# 7_HDMI2.net
KiCad netlist of a schematic drawn in Altium Designer
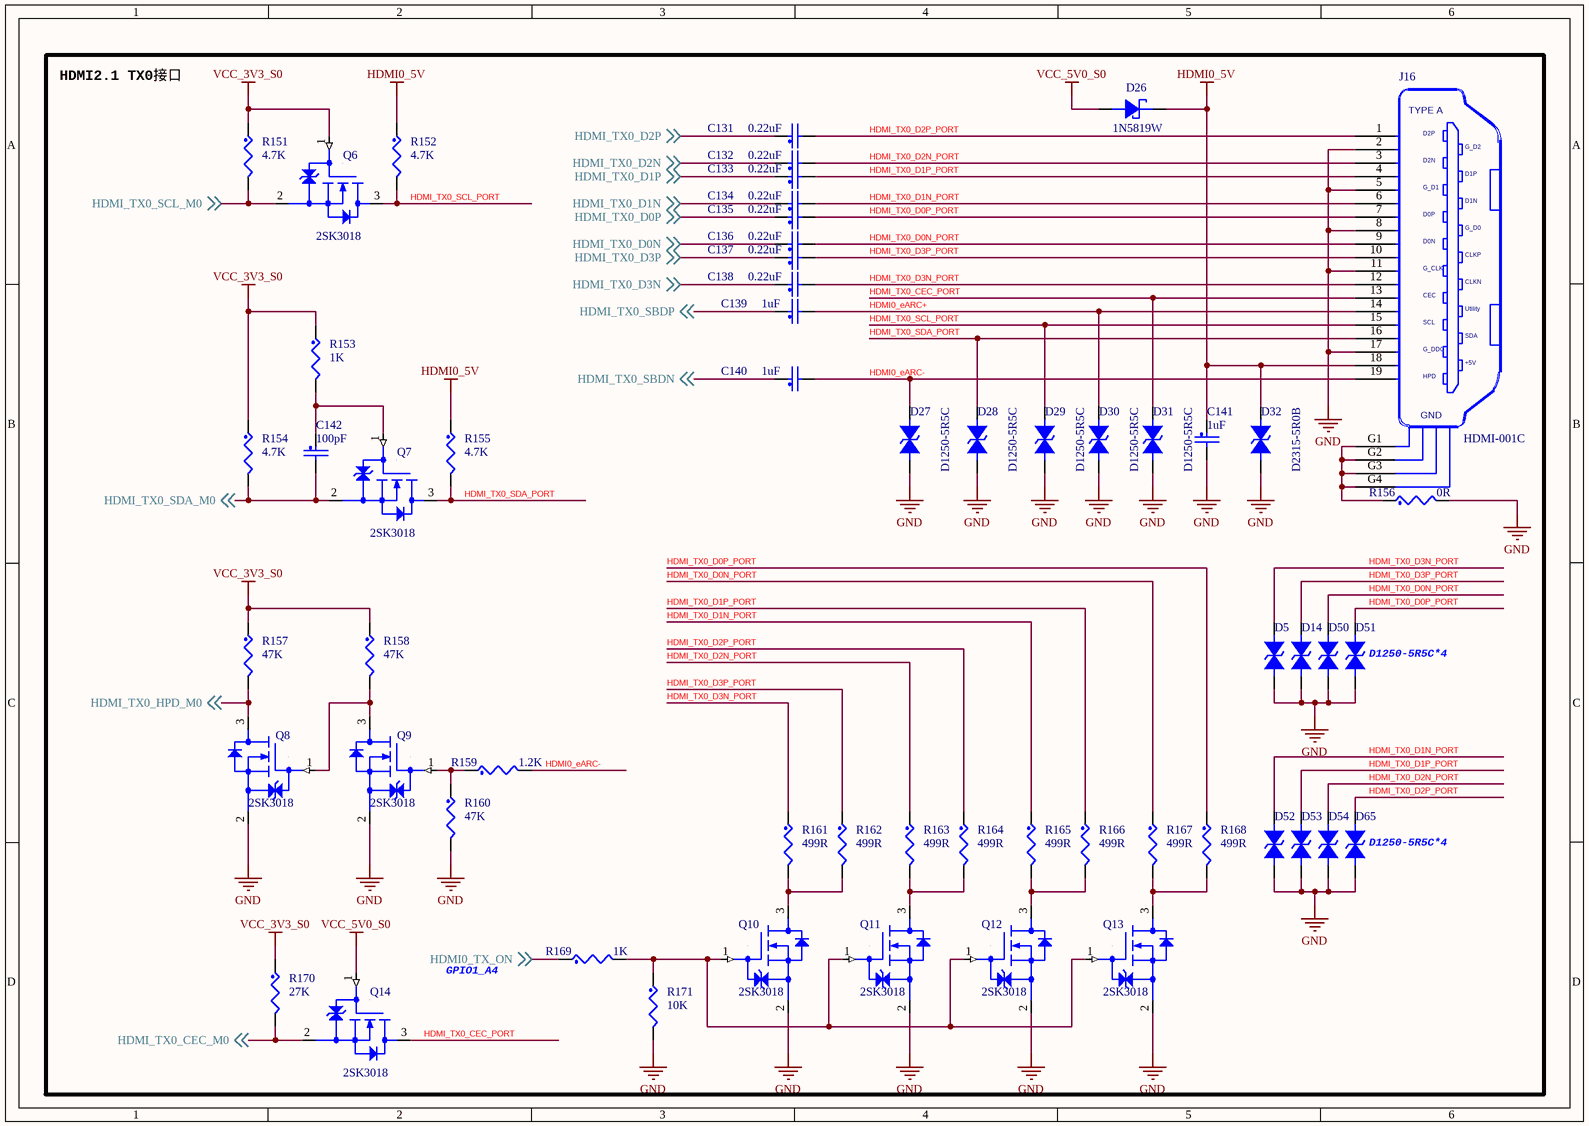
[diagram p0: 7.HDMI2.SchDoc]

(export (version "E")
  (design (tool "Eeschema 10.0.6"))
  (components
    (comp (ref "C131")
      (value "0.22uF")
      (footprint "0.PCB1:C0402")
      (libsource (lib "RK3588底板") (part "CAP_NP"))
    )
    (comp (ref "C132")
      (value "0.22uF")
      (footprint "0.PCB1:C0402")
      (libsource (lib "RK3588底板") (part "CAP_NP"))
    )
    (comp (ref "C133")
      (value "0.22uF")
      (footprint "0.PCB1:C0402")
      (libsource (lib "RK3588底板") (part "CAP_NP"))
    )
    (comp (ref "C134")
      (value "0.22uF")
      (footprint "0.PCB1:C0402")
      (libsource (lib "RK3588底板") (part "CAP_NP"))
    )
    (comp (ref "C135")
      (value "0.22uF")
      (footprint "0.PCB1:C0402")
      (libsource (lib "RK3588底板") (part "CAP_NP"))
    )
    (comp (ref "C136")
      (value "0.22uF")
      (footprint "0.PCB1:C0402")
      (libsource (lib "RK3588底板") (part "CAP_NP"))
    )
    (comp (ref "C137")
      (value "0.22uF")
      (footprint "0.PCB1:C0402")
      (libsource (lib "RK3588底板") (part "CAP_NP"))
    )
    (comp (ref "C138")
      (value "0.22uF")
      (footprint "0.PCB1:C0402")
      (libsource (lib "RK3588底板") (part "CAP_NP"))
    )
    (comp (ref "C139") (value "1uF") (footprint "0.PCB1:C0402") (libsource (lib "RK3588底板") (part "CAP_NP")))
    (comp (ref "C140") (value "1uF") (footprint "0.PCB1:C0402") (libsource (lib "RK3588底板") (part "CAP_NP")))
    (comp (ref "C141") (value "1uF") (footprint "0.PCB1:C0402") (libsource (lib "RK3588底板") (part "CAP_NP")))
    (comp (ref "C142")
      (value "100pF")
      (footprint "0.PCB1:C0402")
      (libsource (lib "RK3588底板") (part "CAP_NP"))
    )
    (comp (ref "D5")
      (value "D1250-5R5C")
      (footprint "0.PCB1:esd0402")
      (libsource (lib "RK3588底板") (part "DIODE BI-DIR TRIG"))
    )
    (comp (ref "D14")
      (value "D1250-5R5C")
      (footprint "0.PCB1:esd0402")
      (libsource (lib "RK3588底板") (part "DIODE BI-DIR TRIG"))
    )
    (comp (ref "D26")
      (value "1N5819W")
      (footprint "0.PCB1:SOD-123")
      (libsource (lib "RK3588底板") (part "DIODE_SCHTKY"))
    )
    (comp (ref "D27")
      (value "D1250-5R5C")
      (footprint "0.PCB1:esd0402")
      (libsource (lib "RK3588底板") (part "DIODE BI-DIR TRIG"))
    )
    (comp (ref "D28")
      (value "D1250-5R5C")
      (footprint "0.PCB1:esd0402")
      (libsource (lib "RK3588底板") (part "DIODE BI-DIR TRIG"))
    )
    (comp (ref "D29")
      (value "D1250-5R5C")
      (footprint "0.PCB1:esd0402")
      (libsource (lib "RK3588底板") (part "DIODE BI-DIR TRIG"))
    )
    (comp (ref "D30")
      (value "D1250-5R5C")
      (footprint "0.PCB1:esd0402")
      (libsource (lib "RK3588底板") (part "DIODE BI-DIR TRIG"))
    )
    (comp (ref "D31")
      (value "D1250-5R5C")
      (footprint "0.PCB1:esd0402")
      (libsource (lib "RK3588底板") (part "DIODE BI-DIR TRIG"))
    )
    (comp (ref "D32")
      (value "D2315-5R0B")
      (footprint "0.PCB1:esd0402")
      (libsource (lib "RK3588底板") (part "DIODE BI-DIR TRIG"))
    )
    (comp (ref "D50")
      (value "D1250-5R5C")
      (footprint "0.PCB1:esd0402")
      (libsource (lib "RK3588底板") (part "DIODE BI-DIR TRIG"))
    )
    (comp (ref "D51")
      (value "D1250-5R5C")
      (footprint "0.PCB1:esd0402")
      (libsource (lib "RK3588底板") (part "DIODE BI-DIR TRIG"))
    )
    (comp (ref "D52")
      (value "D1250-5R5C")
      (footprint "0.PCB1:esd0402")
      (libsource (lib "RK3588底板") (part "DIODE BI-DIR TRIG"))
    )
    (comp (ref "D53")
      (value "D1250-5R5C")
      (footprint "0.PCB1:esd0402")
      (libsource (lib "RK3588底板") (part "DIODE BI-DIR TRIG"))
    )
    (comp (ref "D54")
      (value "D1250-5R5C")
      (footprint "0.PCB1:esd0402")
      (libsource (lib "RK3588底板") (part "DIODE BI-DIR TRIG"))
    )
    (comp (ref "D65")
      (value "D1250-5R5C")
      (footprint "0.PCB1:esd0402")
      (libsource (lib "RK3588底板") (part "DIODE BI-DIR TRIG"))
    )
    (comp (ref "J16")
      (value "HDMI-001C")
      (footprint "0.PCB1:HDMI-SMD")
      (libsource (lib "RK3588底板") (part "HDMI-001C"))
    )
    (comp (ref "Q6")
      (value "2SK3018")
      (footprint "0.PCB1:SOT23")
      (libsource (lib "RK3588底板") (part "2SK3018"))
    )
    (comp (ref "Q7")
      (value "2SK3018")
      (footprint "0.PCB1:SOT23")
      (libsource (lib "RK3588底板") (part "2SK3018"))
    )
    (comp (ref "Q8")
      (value "2SK3018")
      (footprint "0.PCB1:SOT23")
      (libsource (lib "RK3588底板") (part "2SK3018"))
    )
    (comp (ref "Q9")
      (value "2SK3018")
      (footprint "0.PCB1:SOT23")
      (libsource (lib "RK3588底板") (part "2SK3018"))
    )
    (comp (ref "Q10")
      (value "2SK3018")
      (footprint "0.PCB1:SOT23")
      (libsource (lib "RK3588底板") (part "2SK3018"))
    )
    (comp (ref "Q11")
      (value "2SK3018")
      (footprint "0.PCB1:SOT23")
      (libsource (lib "RK3588底板") (part "2SK3018"))
    )
    (comp (ref "Q12")
      (value "2SK3018")
      (footprint "0.PCB1:SOT23")
      (libsource (lib "RK3588底板") (part "2SK3018"))
    )
    (comp (ref "Q13")
      (value "2SK3018")
      (footprint "0.PCB1:SOT23")
      (libsource (lib "RK3588底板") (part "2SK3018"))
    )
    (comp (ref "Q14")
      (value "2SK3018")
      (footprint "0.PCB1:SOT23")
      (libsource (lib "RK3588底板") (part "2SK3018"))
    )
    (comp (ref "R151") (value "4.7K") (footprint "0.PCB1:R0402") (libsource (lib "RK3588底板") (part "RES")))
    (comp (ref "R152") (value "4.7K") (footprint "0.PCB1:R0402") (libsource (lib "RK3588底板") (part "RES")))
    (comp (ref "R153") (value "1K") (footprint "0.PCB1:R0402") (libsource (lib "RK3588底板") (part "RES")))
    (comp (ref "R154") (value "4.7K") (footprint "0.PCB1:R0402") (libsource (lib "RK3588底板") (part "RES")))
    (comp (ref "R155") (value "4.7K") (footprint "0.PCB1:R0402") (libsource (lib "RK3588底板") (part "RES")))
    (comp (ref "R156") (value "0R") (footprint "0.PCB1:R0402") (libsource (lib "RK3588底板") (part "RES")))
    (comp (ref "R157") (value "47K") (footprint "0.PCB1:R0402") (libsource (lib "RK3588底板") (part "RES")))
    (comp (ref "R158") (value "47K") (footprint "0.PCB1:R0402") (libsource (lib "RK3588底板") (part "RES")))
    (comp (ref "R159") (value "1.2K") (footprint "0.PCB1:R0402") (libsource (lib "RK3588底板") (part "RES")))
    (comp (ref "R160") (value "47K") (footprint "0.PCB1:R0402") (libsource (lib "RK3588底板") (part "RES")))
    (comp (ref "R161") (value "499R") (footprint "0.PCB1:R0402") (libsource (lib "RK3588底板") (part "RES")))
    (comp (ref "R162") (value "499R") (footprint "0.PCB1:R0402") (libsource (lib "RK3588底板") (part "RES")))
    (comp (ref "R163") (value "499R") (footprint "0.PCB1:R0402") (libsource (lib "RK3588底板") (part "RES")))
    (comp (ref "R164") (value "499R") (footprint "0.PCB1:R0402") (libsource (lib "RK3588底板") (part "RES")))
    (comp (ref "R165") (value "499R") (footprint "0.PCB1:R0402") (libsource (lib "RK3588底板") (part "RES")))
    (comp (ref "R166") (value "499R") (footprint "0.PCB1:R0402") (libsource (lib "RK3588底板") (part "RES")))
    (comp (ref "R167") (value "499R") (footprint "0.PCB1:R0402") (libsource (lib "RK3588底板") (part "RES")))
    (comp (ref "R168") (value "499R") (footprint "0.PCB1:R0402") (libsource (lib "RK3588底板") (part "RES")))
    (comp (ref "R169") (value "1K") (footprint "0.PCB1:R0402") (libsource (lib "RK3588底板") (part "RES")))
    (comp (ref "R170") (value "27K") (footprint "0.PCB1:R0402") (libsource (lib "RK3588底板") (part "RES")))
    (comp (ref "R171") (value "10K") (footprint "0.PCB1:R0402") (libsource (lib "RK3588底板") (part "RES")))
  )
  (nets
    (net (code "1") (name "/HDMI0_eARC+") (class "Default")
      (node (ref "C139") (pin "2") (pinfunction "2_2") (pintype "passive"))
      (node (ref "D30") (pin "2") (pinfunction "2_2") (pintype "passive"))
      (node (ref "J16") (pin "14") (pinfunction "14_14") (pintype "passive"))
    )
    (net (code "2") (name "/HDMI0_eARC-") (class "Default")
      (node (ref "C140") (pin "2") (pinfunction "2_2") (pintype "passive"))
      (node (ref "D27") (pin "2") (pinfunction "2_2") (pintype "passive"))
      (node (ref "J16") (pin "19") (pinfunction "19_19") (pintype "passive"))
      (node (ref "R159") (pin "2") (pinfunction "2_2") (pintype "passive"))
    )
    (net (code "3") (name "/HDMI_TX0_CEC_PORT") (class "Default")
      (node (ref "D31") (pin "2") (pinfunction "2_2") (pintype "passive"))
      (node (ref "J16") (pin "13") (pinfunction "13_13") (pintype "passive"))
      (node (ref "Q14") (pin "3") (pinfunction "DRAIN_3") (pintype "passive"))
    )
    (net (code "4") (name "/HDMI_TX0_D0N_PORT") (class "Default")
      (node (ref "C136") (pin "2") (pinfunction "2_2") (pintype "passive"))
      (node (ref "D50") (pin "2") (pinfunction "2_2") (pintype "passive"))
      (node (ref "J16") (pin "9") (pinfunction "9_9") (pintype "passive"))
      (node (ref "R167") (pin "1") (pinfunction "1_1") (pintype "passive"))
    )
    (net (code "5") (name "/HDMI_TX0_D0P_PORT") (class "Default")
      (node (ref "C135") (pin "2") (pinfunction "2_2") (pintype "passive"))
      (node (ref "D51") (pin "2") (pinfunction "2_2") (pintype "passive"))
      (node (ref "J16") (pin "7") (pinfunction "7_7") (pintype "passive"))
      (node (ref "R168") (pin "1") (pinfunction "1_1") (pintype "passive"))
    )
    (net (code "6") (name "/HDMI_TX0_D1N_PORT") (class "Default")
      (node (ref "C134") (pin "2") (pinfunction "2_2") (pintype "passive"))
      (node (ref "D52") (pin "2") (pinfunction "2_2") (pintype "passive"))
      (node (ref "J16") (pin "6") (pinfunction "6_6") (pintype "passive"))
      (node (ref "R165") (pin "1") (pinfunction "1_1") (pintype "passive"))
    )
    (net (code "7") (name "/HDMI_TX0_D1P_PORT") (class "Default")
      (node (ref "C133") (pin "2") (pinfunction "2_2") (pintype "passive"))
      (node (ref "D53") (pin "2") (pinfunction "2_2") (pintype "passive"))
      (node (ref "J16") (pin "4") (pinfunction "4_4") (pintype "passive"))
      (node (ref "R166") (pin "1") (pinfunction "1_1") (pintype "passive"))
    )
    (net (code "8") (name "/HDMI_TX0_D2N_PORT") (class "Default")
      (node (ref "C132") (pin "2") (pinfunction "2_2") (pintype "passive"))
      (node (ref "D54") (pin "2") (pinfunction "2_2") (pintype "passive"))
      (node (ref "J16") (pin "3") (pinfunction "3_3") (pintype "passive"))
      (node (ref "R163") (pin "1") (pinfunction "1_1") (pintype "passive"))
    )
    (net (code "9") (name "/HDMI_TX0_D2P_PORT") (class "Default")
      (node (ref "C131") (pin "2") (pinfunction "2_2") (pintype "passive"))
      (node (ref "D65") (pin "2") (pinfunction "2_2") (pintype "passive"))
      (node (ref "J16") (pin "1") (pinfunction "1_1") (pintype "passive"))
      (node (ref "R164") (pin "1") (pinfunction "1_1") (pintype "passive"))
    )
    (net (code "10") (name "/HDMI_TX0_D3N_PORT") (class "Default")
      (node (ref "C138") (pin "2") (pinfunction "2_2") (pintype "passive"))
      (node (ref "D5") (pin "2") (pinfunction "2_2") (pintype "passive"))
      (node (ref "J16") (pin "12") (pinfunction "12_12") (pintype "passive"))
      (node (ref "R161") (pin "1") (pinfunction "1_1") (pintype "passive"))
    )
    (net (code "11") (name "/HDMI_TX0_D3P_PORT") (class "Default")
      (node (ref "C137") (pin "2") (pinfunction "2_2") (pintype "passive"))
      (node (ref "D14") (pin "2") (pinfunction "2_2") (pintype "passive"))
      (node (ref "J16") (pin "10") (pinfunction "10_10") (pintype "passive"))
      (node (ref "R162") (pin "1") (pinfunction "1_1") (pintype "passive"))
    )
    (net (code "12") (name "/HDMI_TX0_SCL_PORT") (class "Default")
      (node (ref "D29") (pin "2") (pinfunction "2_2") (pintype "passive"))
      (node (ref "J16") (pin "15") (pinfunction "15_15") (pintype "passive"))
      (node (ref "Q6") (pin "3") (pinfunction "DRAIN_3") (pintype "passive"))
      (node (ref "R152") (pin "2") (pinfunction "2_2") (pintype "passive"))
    )
    (net (code "13") (name "/HDMI_TX0_SDA_PORT") (class "Default")
      (node (ref "D28") (pin "2") (pinfunction "2_2") (pintype "passive"))
      (node (ref "J16") (pin "16") (pinfunction "16_16") (pintype "passive"))
      (node (ref "Q7") (pin "3") (pinfunction "DRAIN_3") (pintype "passive"))
      (node (ref "R155") (pin "2") (pinfunction "2_2") (pintype "passive"))
    )
    (net (code "14") (name "GND") (class "Default")
      (node (ref "C141") (pin "2") (pinfunction "2_2") (pintype "passive"))
      (node (ref "D14") (pin "1") (pinfunction "1_1") (pintype "passive"))
      (node (ref "D27") (pin "1") (pinfunction "1_1") (pintype "passive"))
      (node (ref "D28") (pin "1") (pinfunction "1_1") (pintype "passive"))
      (node (ref "D29") (pin "1") (pinfunction "1_1") (pintype "passive"))
      (node (ref "D30") (pin "1") (pinfunction "1_1") (pintype "passive"))
      (node (ref "D31") (pin "1") (pinfunction "1_1") (pintype "passive"))
      (node (ref "D32") (pin "1") (pinfunction "1_1") (pintype "passive"))
      (node (ref "D5") (pin "1") (pinfunction "1_1") (pintype "passive"))
      (node (ref "D50") (pin "1") (pinfunction "1_1") (pintype "passive"))
      (node (ref "D51") (pin "1") (pinfunction "1_1") (pintype "passive"))
      (node (ref "D52") (pin "1") (pinfunction "1_1") (pintype "passive"))
      (node (ref "D53") (pin "1") (pinfunction "1_1") (pintype "passive"))
      (node (ref "D54") (pin "1") (pinfunction "1_1") (pintype "passive"))
      (node (ref "D65") (pin "1") (pinfunction "1_1") (pintype "passive"))
      (node (ref "J16") (pin "11") (pinfunction "11_11") (pintype "passive"))
      (node (ref "J16") (pin "17") (pinfunction "17_17") (pintype "passive"))
      (node (ref "J16") (pin "2") (pinfunction "2_2") (pintype "passive"))
      (node (ref "J16") (pin "5") (pinfunction "5_5") (pintype "passive"))
      (node (ref "J16") (pin "8") (pinfunction "8_8") (pintype "passive"))
      (node (ref "Q10") (pin "2") (pinfunction "SOURCE_2") (pintype "passive"))
      (node (ref "Q11") (pin "2") (pinfunction "SOURCE_2") (pintype "passive"))
      (node (ref "Q12") (pin "2") (pinfunction "SOURCE_2") (pintype "passive"))
      (node (ref "Q13") (pin "2") (pinfunction "SOURCE_2") (pintype "passive"))
      (node (ref "Q8") (pin "2") (pinfunction "SOURCE_2") (pintype "passive"))
      (node (ref "Q9") (pin "2") (pinfunction "SOURCE_2") (pintype "passive"))
      (node (ref "R156") (pin "2") (pinfunction "2_2") (pintype "passive"))
      (node (ref "R160") (pin "2") (pinfunction "2_2") (pintype "passive"))
      (node (ref "R171") (pin "2") (pinfunction "2_2") (pintype "passive"))
    )
    (net (code "15") (name "HDMI0_5V") (class "Default")
      (node (ref "C141") (pin "1") (pinfunction "1_1") (pintype "passive"))
      (node (ref "D26") (pin "1") (pinfunction "1_1") (pintype "passive"))
      (node (ref "D32") (pin "2") (pinfunction "2_2") (pintype "passive"))
      (node (ref "J16") (pin "18") (pinfunction "18_18") (pintype "passive"))
      (node (ref "R152") (pin "1") (pinfunction "1_1") (pintype "passive"))
      (node (ref "R155") (pin "1") (pinfunction "1_1") (pintype "passive"))
    )
    (net (code "16") (name "HDMI0_TX_ON") (class "Default")
      (node (ref "R169") (pin "1") (pinfunction "1_1") (pintype "passive"))
    )
    (net (code "17") (name "HDMI_TX0_CEC_M0") (class "Default")
      (node (ref "Q14") (pin "2") (pinfunction "SOURCE_2") (pintype "passive"))
      (node (ref "R170") (pin "2") (pinfunction "2_2") (pintype "passive"))
    )
    (net (code "18") (name "HDMI_TX0_D0N") (class "Default")
      (node (ref "C136") (pin "1") (pinfunction "1_1") (pintype "passive"))
    )
    (net (code "19") (name "HDMI_TX0_D0P") (class "Default")
      (node (ref "C135") (pin "1") (pinfunction "1_1") (pintype "passive"))
    )
    (net (code "20") (name "HDMI_TX0_D1N") (class "Default")
      (node (ref "C134") (pin "1") (pinfunction "1_1") (pintype "passive"))
    )
    (net (code "21") (name "HDMI_TX0_D1P") (class "Default")
      (node (ref "C133") (pin "1") (pinfunction "1_1") (pintype "passive"))
    )
    (net (code "22") (name "HDMI_TX0_D2N") (class "Default")
      (node (ref "C132") (pin "1") (pinfunction "1_1") (pintype "passive"))
    )
    (net (code "23") (name "HDMI_TX0_D2P") (class "Default")
      (node (ref "C131") (pin "1") (pinfunction "1_1") (pintype "passive"))
    )
    (net (code "24") (name "HDMI_TX0_D3N") (class "Default")
      (node (ref "C138") (pin "1") (pinfunction "1_1") (pintype "passive"))
    )
    (net (code "25") (name "HDMI_TX0_D3P") (class "Default")
      (node (ref "C137") (pin "1") (pinfunction "1_1") (pintype "passive"))
    )
    (net (code "26") (name "HDMI_TX0_HPD_M0") (class "Default")
      (node (ref "Q8") (pin "3") (pinfunction "DRAIN_3") (pintype "passive"))
      (node (ref "R157") (pin "2") (pinfunction "2_2") (pintype "passive"))
    )
    (net (code "27") (name "HDMI_TX0_SBDN") (class "Default")
      (node (ref "C140") (pin "1") (pinfunction "1_1") (pintype "passive"))
    )
    (net (code "28") (name "HDMI_TX0_SBDP") (class "Default")
      (node (ref "C139") (pin "1") (pinfunction "1_1") (pintype "passive"))
    )
    (net (code "29") (name "HDMI_TX0_SCL_M0") (class "Default")
      (node (ref "Q6") (pin "2") (pinfunction "SOURCE_2") (pintype "passive"))
      (node (ref "R151") (pin "2") (pinfunction "2_2") (pintype "passive"))
    )
    (net (code "30") (name "HDMI_TX0_SDA_M0") (class "Default")
      (node (ref "C142") (pin "2") (pinfunction "2_2") (pintype "passive"))
      (node (ref "Q7") (pin "2") (pinfunction "SOURCE_2") (pintype "passive"))
      (node (ref "R154") (pin "2") (pinfunction "2_2") (pintype "passive"))
    )
    (net (code "31") (name "Net-(J16-20)") (class "Default")
      (node (ref "J16") (pin "G1") (pinfunction "20_G1") (pintype "passive"))
      (node (ref "J16") (pin "G2") (pinfunction "21_G2") (pintype "passive"))
      (node (ref "J16") (pin "G3") (pinfunction "22_G3") (pintype "passive"))
      (node (ref "J16") (pin "G4") (pinfunction "23_G4") (pintype "passive"))
      (node (ref "R156") (pin "1") (pinfunction "1_1") (pintype "passive"))
    )
    (net (code "32") (name "Net-(Q7-GATE)") (class "Default")
      (node (ref "C142") (pin "1") (pinfunction "1_1") (pintype "passive"))
      (node (ref "Q7") (pin "1") (pinfunction "GATE_1") (pintype "input"))
      (node (ref "R153") (pin "2") (pinfunction "2_2") (pintype "passive"))
    )
    (net (code "33") (name "Net-(Q8-GATE)") (class "Default")
      (node (ref "Q8") (pin "1") (pinfunction "GATE_1") (pintype "input"))
      (node (ref "Q9") (pin "3") (pinfunction "DRAIN_3") (pintype "passive"))
      (node (ref "R158") (pin "2") (pinfunction "2_2") (pintype "passive"))
    )
    (net (code "34") (name "Net-(Q9-GATE)") (class "Default")
      (node (ref "Q9") (pin "1") (pinfunction "GATE_1") (pintype "input"))
      (node (ref "R159") (pin "1") (pinfunction "1_1") (pintype "passive"))
      (node (ref "R160") (pin "1") (pinfunction "1_1") (pintype "passive"))
    )
    (net (code "35") (name "Net-(Q10-DRAIN)") (class "Default")
      (node (ref "Q10") (pin "3") (pinfunction "DRAIN_3") (pintype "passive"))
      (node (ref "R161") (pin "2") (pinfunction "2_2") (pintype "passive"))
      (node (ref "R162") (pin "2") (pinfunction "2_2") (pintype "passive"))
    )
    (net (code "36") (name "Net-(Q10-GATE)") (class "Default")
      (node (ref "Q10") (pin "1") (pinfunction "GATE_1") (pintype "input"))
      (node (ref "Q11") (pin "1") (pinfunction "GATE_1") (pintype "input"))
      (node (ref "Q12") (pin "1") (pinfunction "GATE_1") (pintype "input"))
      (node (ref "Q13") (pin "1") (pinfunction "GATE_1") (pintype "input"))
      (node (ref "R169") (pin "2") (pinfunction "2_2") (pintype "passive"))
      (node (ref "R171") (pin "1") (pinfunction "1_1") (pintype "passive"))
    )
    (net (code "37") (name "Net-(Q11-DRAIN)") (class "Default")
      (node (ref "Q11") (pin "3") (pinfunction "DRAIN_3") (pintype "passive"))
      (node (ref "R163") (pin "2") (pinfunction "2_2") (pintype "passive"))
      (node (ref "R164") (pin "2") (pinfunction "2_2") (pintype "passive"))
    )
    (net (code "38") (name "Net-(Q12-DRAIN)") (class "Default")
      (node (ref "Q12") (pin "3") (pinfunction "DRAIN_3") (pintype "passive"))
      (node (ref "R165") (pin "2") (pinfunction "2_2") (pintype "passive"))
      (node (ref "R166") (pin "2") (pinfunction "2_2") (pintype "passive"))
    )
    (net (code "39") (name "Net-(Q13-DRAIN)") (class "Default")
      (node (ref "Q13") (pin "3") (pinfunction "DRAIN_3") (pintype "passive"))
      (node (ref "R167") (pin "2") (pinfunction "2_2") (pintype "passive"))
      (node (ref "R168") (pin "2") (pinfunction "2_2") (pintype "passive"))
    )
    (net (code "40") (name "VCC_3V3_S0") (class "Default")
      (node (ref "Q6") (pin "1") (pinfunction "GATE_1") (pintype "input"))
      (node (ref "R151") (pin "1") (pinfunction "1_1") (pintype "passive"))
      (node (ref "R153") (pin "1") (pinfunction "1_1") (pintype "passive"))
      (node (ref "R154") (pin "1") (pinfunction "1_1") (pintype "passive"))
      (node (ref "R157") (pin "1") (pinfunction "1_1") (pintype "passive"))
      (node (ref "R158") (pin "1") (pinfunction "1_1") (pintype "passive"))
      (node (ref "R170") (pin "1") (pinfunction "1_1") (pintype "passive"))
    )
    (net (code "41") (name "VCC_5V0_S0") (class "Default")
      (node (ref "D26") (pin "2") (pinfunction "2_2") (pintype "passive"))
      (node (ref "Q14") (pin "1") (pinfunction "GATE_1") (pintype "input"))
    )
  )
)
